# config-bank0.net
KiCad netlist of a schematic drawn in Altium Designer
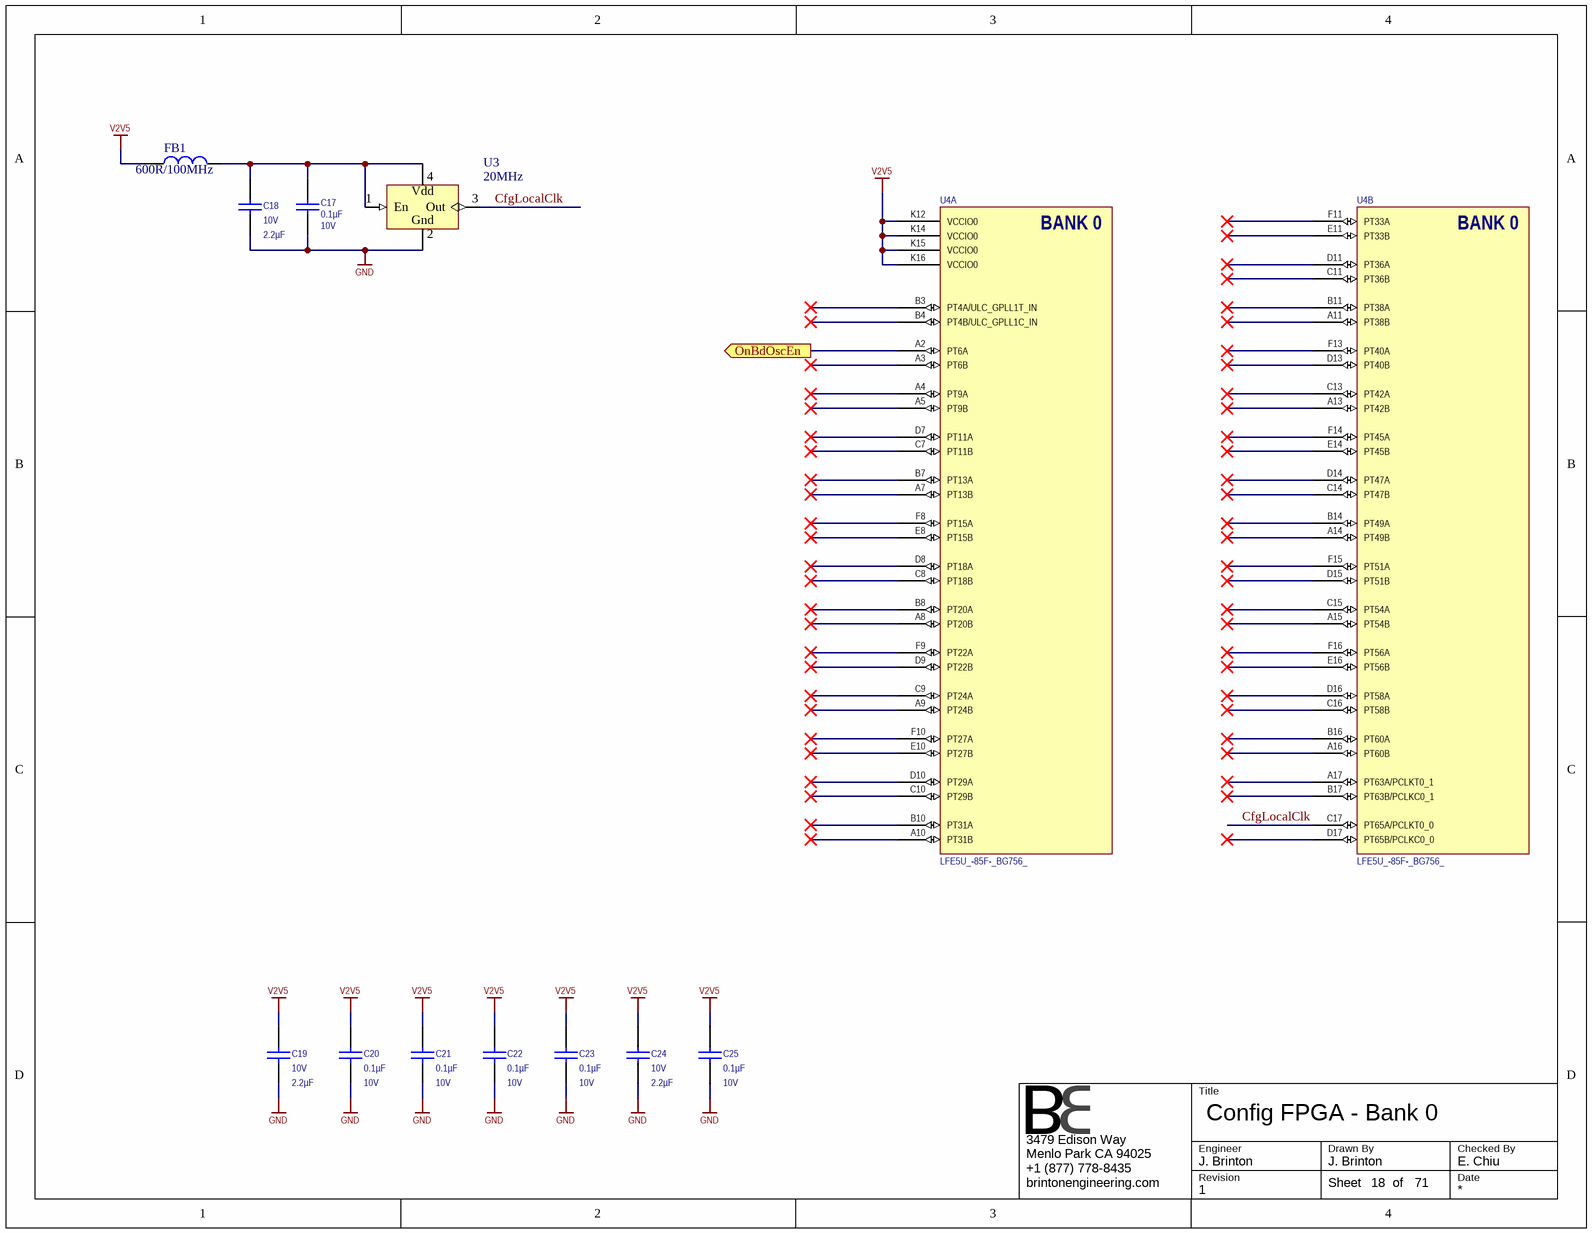
[diagram p0: config-bank0.SchDoc]

(export (version "E")
  (design (tool "Eeschema 10.0.6"))
  (components
    (comp (ref "C17")
      (value "GRM155R71A104KA01J")
      (footprint "CAPC1005X56N")
      (description "CAP CER 0.1UF 10V 10% X7R 0402")
      (fields
        (field (name "MANUFACTURER") "Murata Electronics North America")
        (field (name "TOLERANCE") "±10%")
        (field (name "CAPACITANCE") "0.1µF")
        (field (name "VOLTAGE - RATED") "10V")
      )
      (libsource (lib "murata") (part "GRM155R71A104KA01J"))
    )
    (comp (ref "C18")
      (value "GRM188R71A225KE15D")
      (footprint "CAPC1608X90N")
      (description "CAP CER 2.2UF 10V 10% X7R 0603")
      (fields
        (field (name "MANUFACTURER") "Murata Electronics North America")
        (field (name "TOLERANCE") "±10%")
        (field (name "VOLTAGE - RATED") "10V")
        (field (name "CAPACITANCE") "2.2µF")
      )
      (libsource (lib "murata") (part "GRM188R71A225KE15D"))
    )
    (comp (ref "C19")
      (value "GRM188R71A225KE15D")
      (footprint "CAPC1608X90N")
      (description "CAP CER 2.2UF 10V 10% X7R 0603")
      (fields
        (field (name "MANUFACTURER") "Murata Electronics North America")
        (field (name "TOLERANCE") "±10%")
        (field (name "VOLTAGE - RATED") "10V")
        (field (name "CAPACITANCE") "2.2µF")
      )
      (libsource (lib "murata") (part "GRM188R71A225KE15D"))
    )
    (comp (ref "C20")
      (value "GRM155R71A104KA01J")
      (footprint "CAPC1005X56N")
      (description "CAP CER 0.1UF 10V 10% X7R 0402")
      (fields
        (field (name "MANUFACTURER") "Murata Electronics North America")
        (field (name "TOLERANCE") "±10%")
        (field (name "CAPACITANCE") "0.1µF")
        (field (name "VOLTAGE - RATED") "10V")
      )
      (libsource (lib "murata") (part "GRM155R71A104KA01J"))
    )
    (comp (ref "C21")
      (value "GRM155R71A104KA01J")
      (footprint "CAPC1005X56N")
      (description "CAP CER 0.1UF 10V 10% X7R 0402")
      (fields
        (field (name "MANUFACTURER") "Murata Electronics North America")
        (field (name "TOLERANCE") "±10%")
        (field (name "CAPACITANCE") "0.1µF")
        (field (name "VOLTAGE - RATED") "10V")
      )
      (libsource (lib "murata") (part "GRM155R71A104KA01J"))
    )
    (comp (ref "C22")
      (value "GRM155R71A104KA01J")
      (footprint "CAPC1005X56N")
      (description "CAP CER 0.1UF 10V 10% X7R 0402")
      (fields
        (field (name "MANUFACTURER") "Murata Electronics North America")
        (field (name "TOLERANCE") "±10%")
        (field (name "CAPACITANCE") "0.1µF")
        (field (name "VOLTAGE - RATED") "10V")
      )
      (libsource (lib "murata") (part "GRM155R71A104KA01J"))
    )
    (comp (ref "C23")
      (value "GRM155R71A104KA01J")
      (footprint "CAPC1005X56N")
      (description "CAP CER 0.1UF 10V 10% X7R 0402")
      (fields
        (field (name "MANUFACTURER") "Murata Electronics North America")
        (field (name "TOLERANCE") "±10%")
        (field (name "CAPACITANCE") "0.1µF")
        (field (name "VOLTAGE - RATED") "10V")
      )
      (libsource (lib "murata") (part "GRM155R71A104KA01J"))
    )
    (comp (ref "C24")
      (value "GRM188R71A225KE15D")
      (footprint "CAPC1608X90N")
      (description "CAP CER 2.2UF 10V 10% X7R 0603")
      (fields
        (field (name "MANUFACTURER") "Murata Electronics North America")
        (field (name "TOLERANCE") "±10%")
        (field (name "VOLTAGE - RATED") "10V")
        (field (name "CAPACITANCE") "2.2µF")
      )
      (libsource (lib "murata") (part "GRM188R71A225KE15D"))
    )
    (comp (ref "C25")
      (value "GRM155R71A104KA01J")
      (footprint "CAPC1005X56N")
      (description "CAP CER 0.1UF 10V 10% X7R 0402")
      (fields
        (field (name "MANUFACTURER") "Murata Electronics North America")
        (field (name "TOLERANCE") "±10%")
        (field (name "CAPACITANCE") "0.1µF")
        (field (name "VOLTAGE - RATED") "10V")
      )
      (libsource (lib "murata") (part "GRM155R71A104KA01J"))
    )
    (comp (ref "FB1")
      (value "600R/100MHz")
      (footprint "0805")
      (description "inductance")
      (libsource (lib "*") (part "INDUCTANCE1"))
    )
    (comp (ref "U3")
      (value "20MHz")
      (footprint "OSC2.5X2P")
      (description "IC Oscillator 20MHz 1.8-3.3V 50ppm 2.5x2mm")
      (fields (field (name "MFG") "SiTIME"))
      (libsource (lib "Kron Library Rev 3") (part "KC2520B20.0000C1GE00"))
    )
    (comp (ref "U4")
      (value "LFE5U_-85F-_BG756_")
      (footprint "lattice:caBGA756")
      (description "ECP5 FPGA, 85k LUT, 756-caBGA")
      (fields (field (name "MANUFACTURER") "Lattice Semiconductor"))
      (libsource (lib "lattice") (part "LFE5U_-85F-_BG756_"))
    )
  )
  (nets
    (net (code "1") (name "/CfgLocalClk") (class "Default")
      (node (ref "U3") (pin "3") (pinfunction "Out_3") (pintype "output"))
      (node (ref "U4") (pin "C17") (pinfunction "PT65A/PCLKT0_0_C17") (pintype "bidirectional"))
    )
    (net (code "2") (name "/OnBdOscEn") (class "Default")
      (node (ref "U4") (pin "A2") (pinfunction "PT6A_A2") (pintype "bidirectional"))
    )
    (net (code "3") (name "GND") (class "Default")
      (node (ref "C17") (pin "1") (pinfunction "1_1") (pintype "passive"))
      (node (ref "C18") (pin "1") (pinfunction "1_1") (pintype "passive"))
      (node (ref "C19") (pin "1") (pinfunction "1_1") (pintype "passive"))
      (node (ref "C20") (pin "1") (pinfunction "1_1") (pintype "passive"))
      (node (ref "C21") (pin "1") (pinfunction "1_1") (pintype "passive"))
      (node (ref "C22") (pin "1") (pinfunction "1_1") (pintype "passive"))
      (node (ref "C23") (pin "1") (pinfunction "1_1") (pintype "passive"))
      (node (ref "C24") (pin "1") (pinfunction "1_1") (pintype "passive"))
      (node (ref "C25") (pin "1") (pinfunction "1_1") (pintype "passive"))
      (node (ref "U3") (pin "2") (pinfunction "GND_2") (pintype "power_in"))
    )
    (net (code "4") (name "Net-(U3-En)") (class "Default")
      (node (ref "C17") (pin "2") (pinfunction "2_2") (pintype "passive"))
      (node (ref "C18") (pin "2") (pinfunction "2_2") (pintype "passive"))
      (node (ref "FB1") (pin "1") (pinfunction "1_1") (pintype "passive"))
      (node (ref "U3") (pin "1") (pinfunction "En_1") (pintype "input"))
      (node (ref "U3") (pin "4") (pinfunction "Vdd_4") (pintype "power_in"))
    )
    (net (code "5") (name "V2V5") (class "Default")
      (node (ref "C19") (pin "2") (pinfunction "2_2") (pintype "passive"))
      (node (ref "C20") (pin "2") (pinfunction "2_2") (pintype "passive"))
      (node (ref "C21") (pin "2") (pinfunction "2_2") (pintype "passive"))
      (node (ref "C22") (pin "2") (pinfunction "2_2") (pintype "passive"))
      (node (ref "C23") (pin "2") (pinfunction "2_2") (pintype "passive"))
      (node (ref "C24") (pin "2") (pinfunction "2_2") (pintype "passive"))
      (node (ref "C25") (pin "2") (pinfunction "2_2") (pintype "passive"))
      (node (ref "FB1") (pin "2") (pinfunction "2_2") (pintype "passive"))
      (node (ref "U4") (pin "K12") (pinfunction "VCCIO0_K12") (pintype "power_in"))
      (node (ref "U4") (pin "K14") (pinfunction "VCCIO0_K14") (pintype "power_in"))
      (node (ref "U4") (pin "K15") (pinfunction "VCCIO0_K15") (pintype "power_in"))
      (node (ref "U4") (pin "K16") (pinfunction "VCCIO0_K16") (pintype "power_in"))
    )
    (net (code "6") (name "unconnected-(U4A-PT4A{slash}ULC_GPLL1T_IN-PadB3)") (class "Default")
      (node (ref "U4") (pin "B3") (pinfunction "PT4A/ULC_GPLL1T_IN_B3") (pintype "bidirectional+no_connect"))
    )
    (net (code "7") (name "unconnected-(U4A-PT4B{slash}ULC_GPLL1C_IN-PadB4)") (class "Default")
      (node (ref "U4") (pin "B4") (pinfunction "PT4B/ULC_GPLL1C_IN_B4") (pintype "bidirectional+no_connect"))
    )
    (net (code "8") (name "unconnected-(U4A-PT6B-PadA3)") (class "Default")
      (node (ref "U4") (pin "A3") (pinfunction "PT6B_A3") (pintype "bidirectional+no_connect"))
    )
    (net (code "9") (name "unconnected-(U4A-PT9A-PadA4)") (class "Default")
      (node (ref "U4") (pin "A4") (pinfunction "PT9A_A4") (pintype "bidirectional+no_connect"))
    )
    (net (code "10") (name "unconnected-(U4A-PT9B-PadA5)") (class "Default")
      (node (ref "U4") (pin "A5") (pinfunction "PT9B_A5") (pintype "bidirectional+no_connect"))
    )
    (net (code "11") (name "unconnected-(U4A-PT11A-PadD7)") (class "Default")
      (node (ref "U4") (pin "D7") (pinfunction "PT11A_D7") (pintype "bidirectional+no_connect"))
    )
    (net (code "12") (name "unconnected-(U4A-PT11B-PadC7)") (class "Default")
      (node (ref "U4") (pin "C7") (pinfunction "PT11B_C7") (pintype "bidirectional+no_connect"))
    )
    (net (code "13") (name "unconnected-(U4A-PT13A-PadB7)") (class "Default")
      (node (ref "U4") (pin "B7") (pinfunction "PT13A_B7") (pintype "bidirectional+no_connect"))
    )
    (net (code "14") (name "unconnected-(U4A-PT13B-PadA7)") (class "Default")
      (node (ref "U4") (pin "A7") (pinfunction "PT13B_A7") (pintype "bidirectional+no_connect"))
    )
    (net (code "15") (name "unconnected-(U4A-PT15A-PadF8)") (class "Default")
      (node (ref "U4") (pin "F8") (pinfunction "PT15A_F8") (pintype "bidirectional+no_connect"))
    )
    (net (code "16") (name "unconnected-(U4A-PT15B-PadE8)") (class "Default")
      (node (ref "U4") (pin "E8") (pinfunction "PT15B_E8") (pintype "bidirectional+no_connect"))
    )
    (net (code "17") (name "unconnected-(U4A-PT18A-PadD8)") (class "Default")
      (node (ref "U4") (pin "D8") (pinfunction "PT18A_D8") (pintype "bidirectional+no_connect"))
    )
    (net (code "18") (name "unconnected-(U4A-PT18B-PadC8)") (class "Default")
      (node (ref "U4") (pin "C8") (pinfunction "PT18B_C8") (pintype "bidirectional+no_connect"))
    )
    (net (code "19") (name "unconnected-(U4A-PT20A-PadB8)") (class "Default")
      (node (ref "U4") (pin "B8") (pinfunction "PT20A_B8") (pintype "bidirectional+no_connect"))
    )
    (net (code "20") (name "unconnected-(U4A-PT20B-PadA8)") (class "Default")
      (node (ref "U4") (pin "A8") (pinfunction "PT20B_A8") (pintype "bidirectional+no_connect"))
    )
    (net (code "21") (name "unconnected-(U4A-PT22A-PadF9)") (class "Default")
      (node (ref "U4") (pin "F9") (pinfunction "PT22A_F9") (pintype "bidirectional+no_connect"))
    )
    (net (code "22") (name "unconnected-(U4A-PT22B-PadD9)") (class "Default")
      (node (ref "U4") (pin "D9") (pinfunction "PT22B_D9") (pintype "bidirectional+no_connect"))
    )
    (net (code "23") (name "unconnected-(U4A-PT24A-PadC9)") (class "Default")
      (node (ref "U4") (pin "C9") (pinfunction "PT24A_C9") (pintype "bidirectional+no_connect"))
    )
    (net (code "24") (name "unconnected-(U4A-PT24B-PadA9)") (class "Default")
      (node (ref "U4") (pin "A9") (pinfunction "PT24B_A9") (pintype "bidirectional+no_connect"))
    )
    (net (code "25") (name "unconnected-(U4A-PT27A-PadF10)") (class "Default")
      (node (ref "U4") (pin "F10") (pinfunction "PT27A_F10") (pintype "bidirectional+no_connect"))
    )
    (net (code "26") (name "unconnected-(U4A-PT27B-PadE10)") (class "Default")
      (node (ref "U4") (pin "E10") (pinfunction "PT27B_E10") (pintype "bidirectional+no_connect"))
    )
    (net (code "27") (name "unconnected-(U4A-PT29A-PadD10)") (class "Default")
      (node (ref "U4") (pin "D10") (pinfunction "PT29A_D10") (pintype "bidirectional+no_connect"))
    )
    (net (code "28") (name "unconnected-(U4A-PT29B-PadC10)") (class "Default")
      (node (ref "U4") (pin "C10") (pinfunction "PT29B_C10") (pintype "bidirectional+no_connect"))
    )
    (net (code "29") (name "unconnected-(U4A-PT31A-PadB10)") (class "Default")
      (node (ref "U4") (pin "B10") (pinfunction "PT31A_B10") (pintype "bidirectional+no_connect"))
    )
    (net (code "30") (name "unconnected-(U4A-PT31B-PadA10)") (class "Default")
      (node (ref "U4") (pin "A10") (pinfunction "PT31B_A10") (pintype "bidirectional+no_connect"))
    )
    (net (code "31") (name "unconnected-(U4B-PT33A-PadF11)") (class "Default")
      (node (ref "U4") (pin "F11") (pinfunction "PT33A_F11") (pintype "bidirectional+no_connect"))
    )
    (net (code "32") (name "unconnected-(U4B-PT33B-PadE11)") (class "Default")
      (node (ref "U4") (pin "E11") (pinfunction "PT33B_E11") (pintype "bidirectional+no_connect"))
    )
    (net (code "33") (name "unconnected-(U4B-PT36A-PadD11)") (class "Default")
      (node (ref "U4") (pin "D11") (pinfunction "PT36A_D11") (pintype "bidirectional+no_connect"))
    )
    (net (code "34") (name "unconnected-(U4B-PT36B-PadC11)") (class "Default")
      (node (ref "U4") (pin "C11") (pinfunction "PT36B_C11") (pintype "bidirectional+no_connect"))
    )
    (net (code "35") (name "unconnected-(U4B-PT38A-PadB11)") (class "Default")
      (node (ref "U4") (pin "B11") (pinfunction "PT38A_B11") (pintype "bidirectional+no_connect"))
    )
    (net (code "36") (name "unconnected-(U4B-PT38B-PadA11)") (class "Default")
      (node (ref "U4") (pin "A11") (pinfunction "PT38B_A11") (pintype "bidirectional+no_connect"))
    )
    (net (code "37") (name "unconnected-(U4B-PT40A-PadF13)") (class "Default")
      (node (ref "U4") (pin "F13") (pinfunction "PT40A_F13") (pintype "bidirectional+no_connect"))
    )
    (net (code "38") (name "unconnected-(U4B-PT40B-PadD13)") (class "Default")
      (node (ref "U4") (pin "D13") (pinfunction "PT40B_D13") (pintype "bidirectional+no_connect"))
    )
    (net (code "39") (name "unconnected-(U4B-PT42A-PadC13)") (class "Default")
      (node (ref "U4") (pin "C13") (pinfunction "PT42A_C13") (pintype "bidirectional+no_connect"))
    )
    (net (code "40") (name "unconnected-(U4B-PT42B-PadA13)") (class "Default")
      (node (ref "U4") (pin "A13") (pinfunction "PT42B_A13") (pintype "bidirectional+no_connect"))
    )
    (net (code "41") (name "unconnected-(U4B-PT45A-PadF14)") (class "Default")
      (node (ref "U4") (pin "F14") (pinfunction "PT45A_F14") (pintype "bidirectional+no_connect"))
    )
    (net (code "42") (name "unconnected-(U4B-PT45B-PadE14)") (class "Default")
      (node (ref "U4") (pin "E14") (pinfunction "PT45B_E14") (pintype "bidirectional+no_connect"))
    )
    (net (code "43") (name "unconnected-(U4B-PT47A-PadD14)") (class "Default")
      (node (ref "U4") (pin "D14") (pinfunction "PT47A_D14") (pintype "bidirectional+no_connect"))
    )
    (net (code "44") (name "unconnected-(U4B-PT47B-PadC14)") (class "Default")
      (node (ref "U4") (pin "C14") (pinfunction "PT47B_C14") (pintype "bidirectional+no_connect"))
    )
    (net (code "45") (name "unconnected-(U4B-PT49A-PadB14)") (class "Default")
      (node (ref "U4") (pin "B14") (pinfunction "PT49A_B14") (pintype "bidirectional+no_connect"))
    )
    (net (code "46") (name "unconnected-(U4B-PT49B-PadA14)") (class "Default")
      (node (ref "U4") (pin "A14") (pinfunction "PT49B_A14") (pintype "bidirectional+no_connect"))
    )
    (net (code "47") (name "unconnected-(U4B-PT51A-PadF15)") (class "Default")
      (node (ref "U4") (pin "F15") (pinfunction "PT51A_F15") (pintype "bidirectional+no_connect"))
    )
    (net (code "48") (name "unconnected-(U4B-PT51B-PadD15)") (class "Default")
      (node (ref "U4") (pin "D15") (pinfunction "PT51B_D15") (pintype "bidirectional+no_connect"))
    )
    (net (code "49") (name "unconnected-(U4B-PT54A-PadC15)") (class "Default")
      (node (ref "U4") (pin "C15") (pinfunction "PT54A_C15") (pintype "bidirectional+no_connect"))
    )
    (net (code "50") (name "unconnected-(U4B-PT54B-PadA15)") (class "Default")
      (node (ref "U4") (pin "A15") (pinfunction "PT54B_A15") (pintype "bidirectional+no_connect"))
    )
    (net (code "51") (name "unconnected-(U4B-PT56A-PadF16)") (class "Default")
      (node (ref "U4") (pin "F16") (pinfunction "PT56A_F16") (pintype "bidirectional+no_connect"))
    )
    (net (code "52") (name "unconnected-(U4B-PT56B-PadE16)") (class "Default")
      (node (ref "U4") (pin "E16") (pinfunction "PT56B_E16") (pintype "bidirectional+no_connect"))
    )
    (net (code "53") (name "unconnected-(U4B-PT58A-PadD16)") (class "Default")
      (node (ref "U4") (pin "D16") (pinfunction "PT58A_D16") (pintype "bidirectional+no_connect"))
    )
    (net (code "54") (name "unconnected-(U4B-PT58B-PadC16)") (class "Default")
      (node (ref "U4") (pin "C16") (pinfunction "PT58B_C16") (pintype "bidirectional+no_connect"))
    )
    (net (code "55") (name "unconnected-(U4B-PT60A-PadB16)") (class "Default")
      (node (ref "U4") (pin "B16") (pinfunction "PT60A_B16") (pintype "bidirectional+no_connect"))
    )
    (net (code "56") (name "unconnected-(U4B-PT60B-PadA16)") (class "Default")
      (node (ref "U4") (pin "A16") (pinfunction "PT60B_A16") (pintype "bidirectional+no_connect"))
    )
    (net (code "57") (name "unconnected-(U4B-PT63A{slash}PCLKT0_1-PadA17)") (class "Default")
      (node (ref "U4") (pin "A17") (pinfunction "PT63A/PCLKT0_1_A17") (pintype "bidirectional+no_connect"))
    )
    (net (code "58") (name "unconnected-(U4B-PT63B{slash}PCLKC0_1-PadB17)") (class "Default")
      (node (ref "U4") (pin "B17") (pinfunction "PT63B/PCLKC0_1_B17") (pintype "bidirectional+no_connect"))
    )
    (net (code "59") (name "unconnected-(U4B-PT65B{slash}PCLKC0_0-PadD17)") (class "Default")
      (node (ref "U4") (pin "D17") (pinfunction "PT65B/PCLKC0_0_D17") (pintype "bidirectional+no_connect"))
    )
  )
)
